# MEGA_Shield.net
KiCad netlist of a schematic drawn in Altium Designer
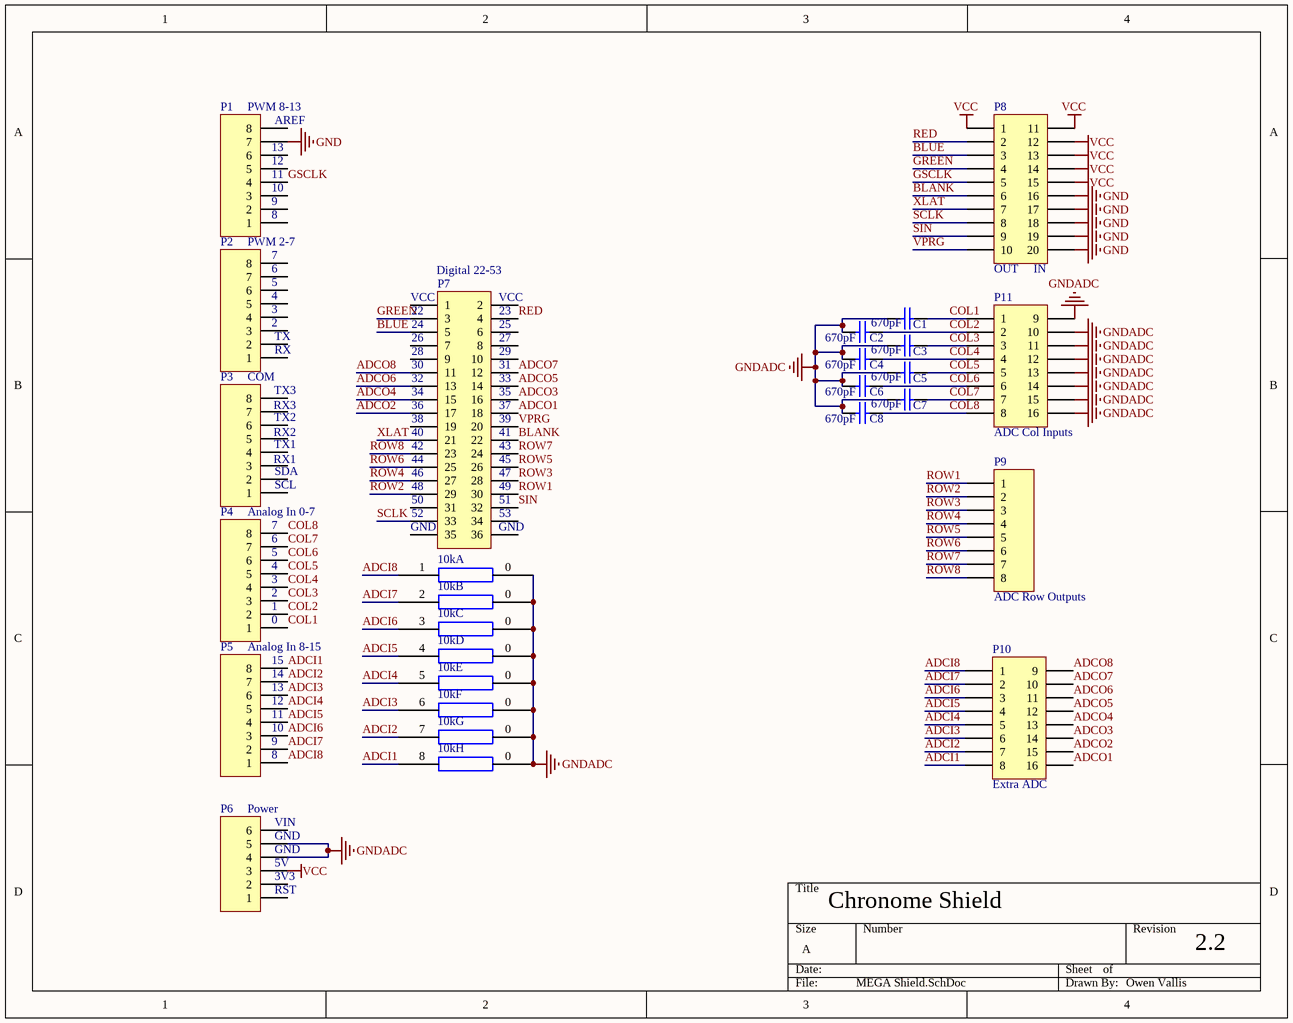
[diagram p0: MEGA Shield.SchDoc]

(export (version "E")
  (design (tool "Eeschema 10.0.6"))
  (components
    (comp (ref "10k")
      (value "Res1")
      (footprint "9-Pin Resistor Network")
      (libsource (lib "RGBPushButton") (part "Res1"))
    )
    (comp (ref "C1")
      (value "670pF")
      (footprint "CAPR2.54-5.1x3.2")
      (description "Capacitor")
      (fields (field (name "Comment") "Cap") (field (name "PUBLISHER") "Altium Limited"))
      (libsource (lib "Miscellaneous Devices") (part "Cap"))
    )
    (comp (ref "C2")
      (value "670pF")
      (footprint "CAPR2.54-5.1x3.2")
      (description "Capacitor")
      (fields (field (name "Comment") "Cap") (field (name "PUBLISHER") "Altium Limited"))
      (libsource (lib "Miscellaneous Devices") (part "Cap"))
    )
    (comp (ref "C3")
      (value "670pF")
      (footprint "CAPR2.54-5.1x3.2")
      (description "Capacitor")
      (fields (field (name "Comment") "Cap") (field (name "PUBLISHER") "Altium Limited"))
      (libsource (lib "Miscellaneous Devices") (part "Cap"))
    )
    (comp (ref "C4")
      (value "670pF")
      (footprint "CAPR2.54-5.1x3.2")
      (description "Capacitor")
      (fields (field (name "Comment") "Cap") (field (name "PUBLISHER") "Altium Limited"))
      (libsource (lib "Miscellaneous Devices") (part "Cap"))
    )
    (comp (ref "C5")
      (value "670pF")
      (footprint "CAPR2.54-5.1x3.2")
      (description "Capacitor")
      (fields (field (name "Comment") "Cap") (field (name "PUBLISHER") "Altium Limited"))
      (libsource (lib "Miscellaneous Devices") (part "Cap"))
    )
    (comp (ref "C6")
      (value "670pF")
      (footprint "CAPR2.54-5.1x3.2")
      (description "Capacitor")
      (fields (field (name "Comment") "Cap") (field (name "PUBLISHER") "Altium Limited"))
      (libsource (lib "Miscellaneous Devices") (part "Cap"))
    )
    (comp (ref "C7")
      (value "670pF")
      (footprint "CAPR2.54-5.1x3.2")
      (description "Capacitor")
      (fields (field (name "Comment") "Cap") (field (name "PUBLISHER") "Altium Limited"))
      (libsource (lib "Miscellaneous Devices") (part "Cap"))
    )
    (comp (ref "C8")
      (value "670pF")
      (footprint "CAPR2.54-5.1x3.2")
      (description "Capacitor")
      (fields (field (name "Comment") "Cap") (field (name "PUBLISHER") "Altium Limited"))
      (libsource (lib "Miscellaneous Devices") (part "Cap"))
    )
    (comp (ref "P1")
      (value "PWM 8-13")
      (footprint "HDR1X8")
      (description "Header, 8-Pin")
      (fields (field (name "PUBLISHER") "Altium Limited"))
      (libsource (lib "Miscellaneous Connectors") (part "Header 8"))
    )
    (comp (ref "P2")
      (value "PWM 2-7")
      (footprint "HDR1X8")
      (description "Header, 8-Pin")
      (fields (field (name "PUBLISHER") "Altium Limited"))
      (libsource (lib "Miscellaneous Connectors") (part "Header 8"))
    )
    (comp (ref "P3")
      (value "COM")
      (footprint "HDR1X8")
      (description "Header, 8-Pin")
      (fields (field (name "PUBLISHER") "Altium Limited"))
      (libsource (lib "Miscellaneous Connectors") (part "Header 8"))
    )
    (comp (ref "P4")
      (value "Analog In 0-7")
      (footprint "HDR1X8")
      (description "Header, 8-Pin")
      (fields (field (name "PUBLISHER") "Altium Limited"))
      (libsource (lib "Miscellaneous Connectors") (part "Header 8"))
    )
    (comp (ref "P5")
      (value "Analog In 8-15")
      (footprint "HDR1X8")
      (description "Header, 8-Pin")
      (fields (field (name "PUBLISHER") "Altium Limited"))
      (libsource (lib "Miscellaneous Connectors") (part "Header 8"))
    )
    (comp (ref "P6")
      (value "Power")
      (footprint "HDR1X6")
      (description "Header, 6-Pin")
      (fields (field (name "PUBLISHER") "Altium Limited"))
      (libsource (lib "Miscellaneous Connectors") (part "Header 6"))
    )
    (comp (ref "P7")
      (value "Digital 22-53")
      (footprint "HDR2X18")
      (description "Header, 18-Pin, Dual row")
      (fields (field (name "PUBLISHER") "Altium Limited"))
      (libsource (lib "Miscellaneous Connectors") (part "Header 18X2"))
    )
    (comp (ref "P8")
      (value "OUT     IN")
      (footprint "HDR2X10_CEN")
      (description "Header, 10-Pin, Dual row")
      (fields (field (name "PUBLISHER") "Altium Limited"))
      (libsource (lib "Miscellaneous Connectors") (part "Header 10X2A"))
    )
    (comp (ref "P9")
      (value "ADC Row Outputs")
      (footprint "HDR1X8")
      (description "Header, 8-Pin")
      (fields (field (name "PUBLISHER") "Altium Limited"))
      (libsource (lib "") (part "Header 8_1"))
    )
    (comp (ref "P10")
      (value "Extra ADC")
      (footprint "HDR2X8_CEN")
      (description "Header, 8-Pin, Dual row")
      (fields (field (name "PUBLISHER") "Altium Limited"))
      (libsource (lib "Miscellaneous Connectors") (part "Header 8X2A"))
    )
    (comp (ref "P11")
      (value "ADC Col Inputs")
      (footprint "HDR2X8_CEN")
      (description "Header, 8-Pin, Dual row")
      (fields (field (name "PUBLISHER") "Altium Limited"))
      (libsource (lib "Miscellaneous Connectors") (part "Header 8X2A"))
    )
  )
  (nets
    (net (code "1") (name "/ADCI1") (class "Default")
      (node (ref "10k") (pin "8") (pinfunction "8_8") (pintype "passive"))
      (node (ref "P10") (pin "8") (pinfunction "8_8") (pintype "passive"))
      (node (ref "P5") (pin "8") (pinfunction "8_8") (pintype "passive"))
    )
    (net (code "2") (name "/ADCI2") (class "Default")
      (node (ref "10k") (pin "7") (pinfunction "7_7") (pintype "passive"))
      (node (ref "P10") (pin "7") (pinfunction "7_7") (pintype "passive"))
      (node (ref "P5") (pin "7") (pinfunction "7_7") (pintype "passive"))
    )
    (net (code "3") (name "/ADCI3") (class "Default")
      (node (ref "10k") (pin "6") (pinfunction "6_6") (pintype "passive"))
      (node (ref "P10") (pin "6") (pinfunction "6_6") (pintype "passive"))
      (node (ref "P5") (pin "6") (pinfunction "6_6") (pintype "passive"))
    )
    (net (code "4") (name "/ADCI4") (class "Default")
      (node (ref "10k") (pin "5") (pinfunction "5_5") (pintype "passive"))
      (node (ref "P10") (pin "5") (pinfunction "5_5") (pintype "passive"))
      (node (ref "P5") (pin "5") (pinfunction "5_5") (pintype "passive"))
    )
    (net (code "5") (name "/ADCI5") (class "Default")
      (node (ref "10k") (pin "4") (pinfunction "4_4") (pintype "passive"))
      (node (ref "P10") (pin "4") (pinfunction "4_4") (pintype "passive"))
      (node (ref "P5") (pin "4") (pinfunction "4_4") (pintype "passive"))
    )
    (net (code "6") (name "/ADCI6") (class "Default")
      (node (ref "10k") (pin "3") (pinfunction "3_3") (pintype "passive"))
      (node (ref "P10") (pin "3") (pinfunction "3_3") (pintype "passive"))
      (node (ref "P5") (pin "3") (pinfunction "3_3") (pintype "passive"))
    )
    (net (code "7") (name "/ADCI7") (class "Default")
      (node (ref "10k") (pin "2") (pinfunction "2_2") (pintype "passive"))
      (node (ref "P10") (pin "2") (pinfunction "2_2") (pintype "passive"))
      (node (ref "P5") (pin "2") (pinfunction "2_2") (pintype "passive"))
    )
    (net (code "8") (name "/ADCI8") (class "Default")
      (node (ref "10k") (pin "1") (pinfunction "1_1") (pintype "passive"))
      (node (ref "P10") (pin "1") (pinfunction "1_1") (pintype "passive"))
      (node (ref "P5") (pin "1") (pinfunction "1_1") (pintype "passive"))
    )
    (net (code "9") (name "/ADCO1") (class "Default")
      (node (ref "P10") (pin "16") (pinfunction "16_16") (pintype "passive"))
      (node (ref "P7") (pin "18") (pinfunction "18_18") (pintype "passive"))
    )
    (net (code "10") (name "/ADCO2") (class "Default")
      (node (ref "P10") (pin "15") (pinfunction "15_15") (pintype "passive"))
      (node (ref "P7") (pin "17") (pinfunction "17_17") (pintype "passive"))
    )
    (net (code "11") (name "/ADCO3") (class "Default")
      (node (ref "P10") (pin "14") (pinfunction "14_14") (pintype "passive"))
      (node (ref "P7") (pin "16") (pinfunction "16_16") (pintype "passive"))
    )
    (net (code "12") (name "/ADCO4") (class "Default")
      (node (ref "P10") (pin "13") (pinfunction "13_13") (pintype "passive"))
      (node (ref "P7") (pin "15") (pinfunction "15_15") (pintype "passive"))
    )
    (net (code "13") (name "/ADCO5") (class "Default")
      (node (ref "P10") (pin "12") (pinfunction "12_12") (pintype "passive"))
      (node (ref "P7") (pin "14") (pinfunction "14_14") (pintype "passive"))
    )
    (net (code "14") (name "/ADCO6") (class "Default")
      (node (ref "P10") (pin "11") (pinfunction "11_11") (pintype "passive"))
      (node (ref "P7") (pin "13") (pinfunction "13_13") (pintype "passive"))
    )
    (net (code "15") (name "/ADCO7") (class "Default")
      (node (ref "P10") (pin "10") (pinfunction "10_10") (pintype "passive"))
      (node (ref "P7") (pin "12") (pinfunction "12_12") (pintype "passive"))
    )
    (net (code "16") (name "/ADCO8") (class "Default")
      (node (ref "P10") (pin "9") (pinfunction "9_9") (pintype "passive"))
      (node (ref "P7") (pin "11") (pinfunction "11_11") (pintype "passive"))
    )
    (net (code "17") (name "/BLANK") (class "Default")
      (node (ref "P7") (pin "22") (pinfunction "22_22") (pintype "passive"))
      (node (ref "P8") (pin "6") (pinfunction "6_6") (pintype "passive"))
    )
    (net (code "18") (name "/BLUE") (class "Default")
      (node (ref "P7") (pin "5") (pinfunction "5_5") (pintype "passive"))
      (node (ref "P8") (pin "3") (pinfunction "3_3") (pintype "passive"))
    )
    (net (code "19") (name "/COL1") (class "Default")
      (node (ref "C1") (pin "2") (pinfunction "2_2") (pintype "passive"))
      (node (ref "P11") (pin "1") (pinfunction "1_1") (pintype "passive"))
      (node (ref "P4") (pin "1") (pinfunction "1_1") (pintype "passive"))
    )
    (net (code "20") (name "/COL2") (class "Default")
      (node (ref "C2") (pin "2") (pinfunction "2_2") (pintype "passive"))
      (node (ref "P11") (pin "2") (pinfunction "2_2") (pintype "passive"))
      (node (ref "P4") (pin "2") (pinfunction "2_2") (pintype "passive"))
    )
    (net (code "21") (name "/COL3") (class "Default")
      (node (ref "C3") (pin "2") (pinfunction "2_2") (pintype "passive"))
      (node (ref "P11") (pin "3") (pinfunction "3_3") (pintype "passive"))
      (node (ref "P4") (pin "3") (pinfunction "3_3") (pintype "passive"))
    )
    (net (code "22") (name "/COL4") (class "Default")
      (node (ref "C4") (pin "2") (pinfunction "2_2") (pintype "passive"))
      (node (ref "P11") (pin "4") (pinfunction "4_4") (pintype "passive"))
      (node (ref "P4") (pin "4") (pinfunction "4_4") (pintype "passive"))
    )
    (net (code "23") (name "/COL5") (class "Default")
      (node (ref "C5") (pin "2") (pinfunction "2_2") (pintype "passive"))
      (node (ref "P11") (pin "5") (pinfunction "5_5") (pintype "passive"))
      (node (ref "P4") (pin "5") (pinfunction "5_5") (pintype "passive"))
    )
    (net (code "24") (name "/COL6") (class "Default")
      (node (ref "C6") (pin "2") (pinfunction "2_2") (pintype "passive"))
      (node (ref "P11") (pin "6") (pinfunction "6_6") (pintype "passive"))
      (node (ref "P4") (pin "6") (pinfunction "6_6") (pintype "passive"))
    )
    (net (code "25") (name "/COL7") (class "Default")
      (node (ref "C7") (pin "2") (pinfunction "2_2") (pintype "passive"))
      (node (ref "P11") (pin "7") (pinfunction "7_7") (pintype "passive"))
      (node (ref "P4") (pin "7") (pinfunction "7_7") (pintype "passive"))
    )
    (net (code "26") (name "/COL8") (class "Default")
      (node (ref "C8") (pin "2") (pinfunction "2_2") (pintype "passive"))
      (node (ref "P11") (pin "8") (pinfunction "8_8") (pintype "passive"))
      (node (ref "P4") (pin "8") (pinfunction "8_8") (pintype "passive"))
    )
    (net (code "27") (name "/GREEN") (class "Default")
      (node (ref "P7") (pin "3") (pinfunction "3_3") (pintype "passive"))
      (node (ref "P8") (pin "4") (pinfunction "4_4") (pintype "passive"))
    )
    (net (code "28") (name "/GSCLK") (class "Default")
      (node (ref "P1") (pin "4") (pinfunction "4_4") (pintype "passive"))
      (node (ref "P8") (pin "5") (pinfunction "5_5") (pintype "passive"))
    )
    (net (code "29") (name "/RED") (class "Default")
      (node (ref "P7") (pin "4") (pinfunction "4_4") (pintype "passive"))
      (node (ref "P8") (pin "2") (pinfunction "2_2") (pintype "passive"))
    )
    (net (code "30") (name "/ROW1") (class "Default")
      (node (ref "P7") (pin "30") (pinfunction "30_30") (pintype "passive"))
      (node (ref "P9") (pin "1") (pinfunction "1_1") (pintype "passive"))
    )
    (net (code "31") (name "/ROW2") (class "Default")
      (node (ref "P7") (pin "29") (pinfunction "29_29") (pintype "passive"))
      (node (ref "P9") (pin "2") (pinfunction "2_2") (pintype "passive"))
    )
    (net (code "32") (name "/ROW3") (class "Default")
      (node (ref "P7") (pin "28") (pinfunction "28_28") (pintype "passive"))
      (node (ref "P9") (pin "3") (pinfunction "3_3") (pintype "passive"))
    )
    (net (code "33") (name "/ROW4") (class "Default")
      (node (ref "P7") (pin "27") (pinfunction "27_27") (pintype "passive"))
      (node (ref "P9") (pin "4") (pinfunction "4_4") (pintype "passive"))
    )
    (net (code "34") (name "/ROW5") (class "Default")
      (node (ref "P7") (pin "26") (pinfunction "26_26") (pintype "passive"))
      (node (ref "P9") (pin "5") (pinfunction "5_5") (pintype "passive"))
    )
    (net (code "35") (name "/ROW6") (class "Default")
      (node (ref "P7") (pin "25") (pinfunction "25_25") (pintype "passive"))
      (node (ref "P9") (pin "6") (pinfunction "6_6") (pintype "passive"))
    )
    (net (code "36") (name "/ROW7") (class "Default")
      (node (ref "P7") (pin "24") (pinfunction "24_24") (pintype "passive"))
      (node (ref "P9") (pin "7") (pinfunction "7_7") (pintype "passive"))
    )
    (net (code "37") (name "/ROW8") (class "Default")
      (node (ref "P7") (pin "23") (pinfunction "23_23") (pintype "passive"))
      (node (ref "P9") (pin "8") (pinfunction "8_8") (pintype "passive"))
    )
    (net (code "38") (name "/SCLK") (class "Default")
      (node (ref "P7") (pin "33") (pinfunction "33_33") (pintype "passive"))
      (node (ref "P8") (pin "8") (pinfunction "8_8") (pintype "passive"))
    )
    (net (code "39") (name "/SIN") (class "Default")
      (node (ref "P7") (pin "32") (pinfunction "32_32") (pintype "passive"))
      (node (ref "P8") (pin "9") (pinfunction "9_9") (pintype "passive"))
    )
    (net (code "40") (name "/VPRG") (class "Default")
      (node (ref "P7") (pin "20") (pinfunction "20_20") (pintype "passive"))
      (node (ref "P8") (pin "10") (pinfunction "10_10") (pintype "passive"))
    )
    (net (code "41") (name "/XLAT") (class "Default")
      (node (ref "P7") (pin "21") (pinfunction "21_21") (pintype "passive"))
      (node (ref "P8") (pin "7") (pinfunction "7_7") (pintype "passive"))
    )
    (net (code "42") (name "GND") (class "Default")
      (node (ref "P1") (pin "7") (pinfunction "7_7") (pintype "passive"))
      (node (ref "P8") (pin "16") (pinfunction "16_16") (pintype "passive"))
      (node (ref "P8") (pin "17") (pinfunction "17_17") (pintype "passive"))
      (node (ref "P8") (pin "18") (pinfunction "18_18") (pintype "passive"))
      (node (ref "P8") (pin "19") (pinfunction "19_19") (pintype "passive"))
      (node (ref "P8") (pin "20") (pinfunction "20_20") (pintype "passive"))
    )
    (net (code "43") (name "GNDADC") (class "Default")
      (node (ref "10k") (pin "0") (pinfunction "0_0") (pintype "passive"))
      (node (ref "C1") (pin "1") (pinfunction "1_1") (pintype "passive"))
      (node (ref "C2") (pin "1") (pinfunction "1_1") (pintype "passive"))
      (node (ref "C3") (pin "1") (pinfunction "1_1") (pintype "passive"))
      (node (ref "C4") (pin "1") (pinfunction "1_1") (pintype "passive"))
      (node (ref "C5") (pin "1") (pinfunction "1_1") (pintype "passive"))
      (node (ref "C6") (pin "1") (pinfunction "1_1") (pintype "passive"))
      (node (ref "C7") (pin "1") (pinfunction "1_1") (pintype "passive"))
      (node (ref "C8") (pin "1") (pinfunction "1_1") (pintype "passive"))
      (node (ref "P11") (pin "10") (pinfunction "10_10") (pintype "passive"))
      (node (ref "P11") (pin "11") (pinfunction "11_11") (pintype "passive"))
      (node (ref "P11") (pin "12") (pinfunction "12_12") (pintype "passive"))
      (node (ref "P11") (pin "13") (pinfunction "13_13") (pintype "passive"))
      (node (ref "P11") (pin "14") (pinfunction "14_14") (pintype "passive"))
      (node (ref "P11") (pin "15") (pinfunction "15_15") (pintype "passive"))
      (node (ref "P11") (pin "16") (pinfunction "16_16") (pintype "passive"))
      (node (ref "P11") (pin "9") (pinfunction "9_9") (pintype "passive"))
      (node (ref "P6") (pin "4") (pinfunction "4_4") (pintype "passive"))
      (node (ref "P6") (pin "5") (pinfunction "5_5") (pintype "passive"))
    )
    (net (code "44") (name "VCC") (class "Default")
      (node (ref "P6") (pin "3") (pinfunction "3_3") (pintype "passive"))
      (node (ref "P8") (pin "1") (pinfunction "1_1") (pintype "passive"))
      (node (ref "P8") (pin "11") (pinfunction "11_11") (pintype "passive"))
      (node (ref "P8") (pin "12") (pinfunction "12_12") (pintype "passive"))
      (node (ref "P8") (pin "13") (pinfunction "13_13") (pintype "passive"))
      (node (ref "P8") (pin "14") (pinfunction "14_14") (pintype "passive"))
      (node (ref "P8") (pin "15") (pinfunction "15_15") (pintype "passive"))
    )
    (net (code "45") (name "unconnected-(P1-Pad1)") (class "Default")
      (node (ref "P1") (pin "1") (pinfunction "1_1") (pintype "passive"))
    )
    (net (code "46") (name "unconnected-(P1-Pad2)") (class "Default")
      (node (ref "P1") (pin "2") (pinfunction "2_2") (pintype "passive"))
    )
    (net (code "47") (name "unconnected-(P1-Pad3)") (class "Default")
      (node (ref "P1") (pin "3") (pinfunction "3_3") (pintype "passive"))
    )
    (net (code "48") (name "unconnected-(P1-Pad5)") (class "Default")
      (node (ref "P1") (pin "5") (pinfunction "5_5") (pintype "passive"))
    )
    (net (code "49") (name "unconnected-(P1-Pad6)") (class "Default")
      (node (ref "P1") (pin "6") (pinfunction "6_6") (pintype "passive"))
    )
    (net (code "50") (name "unconnected-(P1-Pad8)") (class "Default")
      (node (ref "P1") (pin "8") (pinfunction "8_8") (pintype "passive"))
    )
    (net (code "51") (name "unconnected-(P2-Pad1)") (class "Default")
      (node (ref "P2") (pin "1") (pinfunction "1_1") (pintype "passive"))
    )
    (net (code "52") (name "unconnected-(P2-Pad2)") (class "Default")
      (node (ref "P2") (pin "2") (pinfunction "2_2") (pintype "passive"))
    )
    (net (code "53") (name "unconnected-(P2-Pad3)") (class "Default")
      (node (ref "P2") (pin "3") (pinfunction "3_3") (pintype "passive"))
    )
    (net (code "54") (name "unconnected-(P2-Pad4)") (class "Default")
      (node (ref "P2") (pin "4") (pinfunction "4_4") (pintype "passive"))
    )
    (net (code "55") (name "unconnected-(P2-Pad5)") (class "Default")
      (node (ref "P2") (pin "5") (pinfunction "5_5") (pintype "passive"))
    )
    (net (code "56") (name "unconnected-(P2-Pad6)") (class "Default")
      (node (ref "P2") (pin "6") (pinfunction "6_6") (pintype "passive"))
    )
    (net (code "57") (name "unconnected-(P2-Pad7)") (class "Default")
      (node (ref "P2") (pin "7") (pinfunction "7_7") (pintype "passive"))
    )
    (net (code "58") (name "unconnected-(P2-Pad8)") (class "Default")
      (node (ref "P2") (pin "8") (pinfunction "8_8") (pintype "passive"))
    )
    (net (code "59") (name "unconnected-(P3-Pad1)") (class "Default")
      (node (ref "P3") (pin "1") (pinfunction "1_1") (pintype "passive"))
    )
    (net (code "60") (name "unconnected-(P3-Pad2)") (class "Default")
      (node (ref "P3") (pin "2") (pinfunction "2_2") (pintype "passive"))
    )
    (net (code "61") (name "unconnected-(P3-Pad3)") (class "Default")
      (node (ref "P3") (pin "3") (pinfunction "3_3") (pintype "passive"))
    )
    (net (code "62") (name "unconnected-(P3-Pad4)") (class "Default")
      (node (ref "P3") (pin "4") (pinfunction "4_4") (pintype "passive"))
    )
    (net (code "63") (name "unconnected-(P3-Pad5)") (class "Default")
      (node (ref "P3") (pin "5") (pinfunction "5_5") (pintype "passive"))
    )
    (net (code "64") (name "unconnected-(P3-Pad6)") (class "Default")
      (node (ref "P3") (pin "6") (pinfunction "6_6") (pintype "passive"))
    )
    (net (code "65") (name "unconnected-(P3-Pad7)") (class "Default")
      (node (ref "P3") (pin "7") (pinfunction "7_7") (pintype "passive"))
    )
    (net (code "66") (name "unconnected-(P3-Pad8)") (class "Default")
      (node (ref "P3") (pin "8") (pinfunction "8_8") (pintype "passive"))
    )
    (net (code "67") (name "unconnected-(P6-Pad1)") (class "Default")
      (node (ref "P6") (pin "1") (pinfunction "1_1") (pintype "passive"))
    )
    (net (code "68") (name "unconnected-(P6-Pad2)") (class "Default")
      (node (ref "P6") (pin "2") (pinfunction "2_2") (pintype "passive"))
    )
    (net (code "69") (name "unconnected-(P6-Pad6)") (class "Default")
      (node (ref "P6") (pin "6") (pinfunction "6_6") (pintype "passive"))
    )
    (net (code "70") (name "unconnected-(P7-Pad1)") (class "Default")
      (node (ref "P7") (pin "1") (pinfunction "1_1") (pintype "passive"))
    )
    (net (code "71") (name "unconnected-(P7-Pad2)") (class "Default")
      (node (ref "P7") (pin "2") (pinfunction "2_2") (pintype "passive"))
    )
    (net (code "72") (name "unconnected-(P7-Pad6)") (class "Default")
      (node (ref "P7") (pin "6") (pinfunction "6_6") (pintype "passive"))
    )
    (net (code "73") (name "unconnected-(P7-Pad7)") (class "Default")
      (node (ref "P7") (pin "7") (pinfunction "7_7") (pintype "passive"))
    )
    (net (code "74") (name "unconnected-(P7-Pad8)") (class "Default")
      (node (ref "P7") (pin "8") (pinfunction "8_8") (pintype "passive"))
    )
    (net (code "75") (name "unconnected-(P7-Pad9)") (class "Default")
      (node (ref "P7") (pin "9") (pinfunction "9_9") (pintype "passive"))
    )
    (net (code "76") (name "unconnected-(P7-Pad10)") (class "Default")
      (node (ref "P7") (pin "10") (pinfunction "10_10") (pintype "passive"))
    )
    (net (code "77") (name "unconnected-(P7-Pad19)") (class "Default")
      (node (ref "P7") (pin "19") (pinfunction "19_19") (pintype "passive"))
    )
    (net (code "78") (name "unconnected-(P7-Pad31)") (class "Default")
      (node (ref "P7") (pin "31") (pinfunction "31_31") (pintype "passive"))
    )
    (net (code "79") (name "unconnected-(P7-Pad34)") (class "Default")
      (node (ref "P7") (pin "34") (pinfunction "34_34") (pintype "passive"))
    )
    (net (code "80") (name "unconnected-(P7-Pad35)") (class "Default")
      (node (ref "P7") (pin "35") (pinfunction "35_35") (pintype "passive"))
    )
    (net (code "81") (name "unconnected-(P7-Pad36)") (class "Default")
      (node (ref "P7") (pin "36") (pinfunction "36_36") (pintype "passive"))
    )
  )
)
